# MiniCob.net
KiCad netlist of a schematic drawn in EAGLE
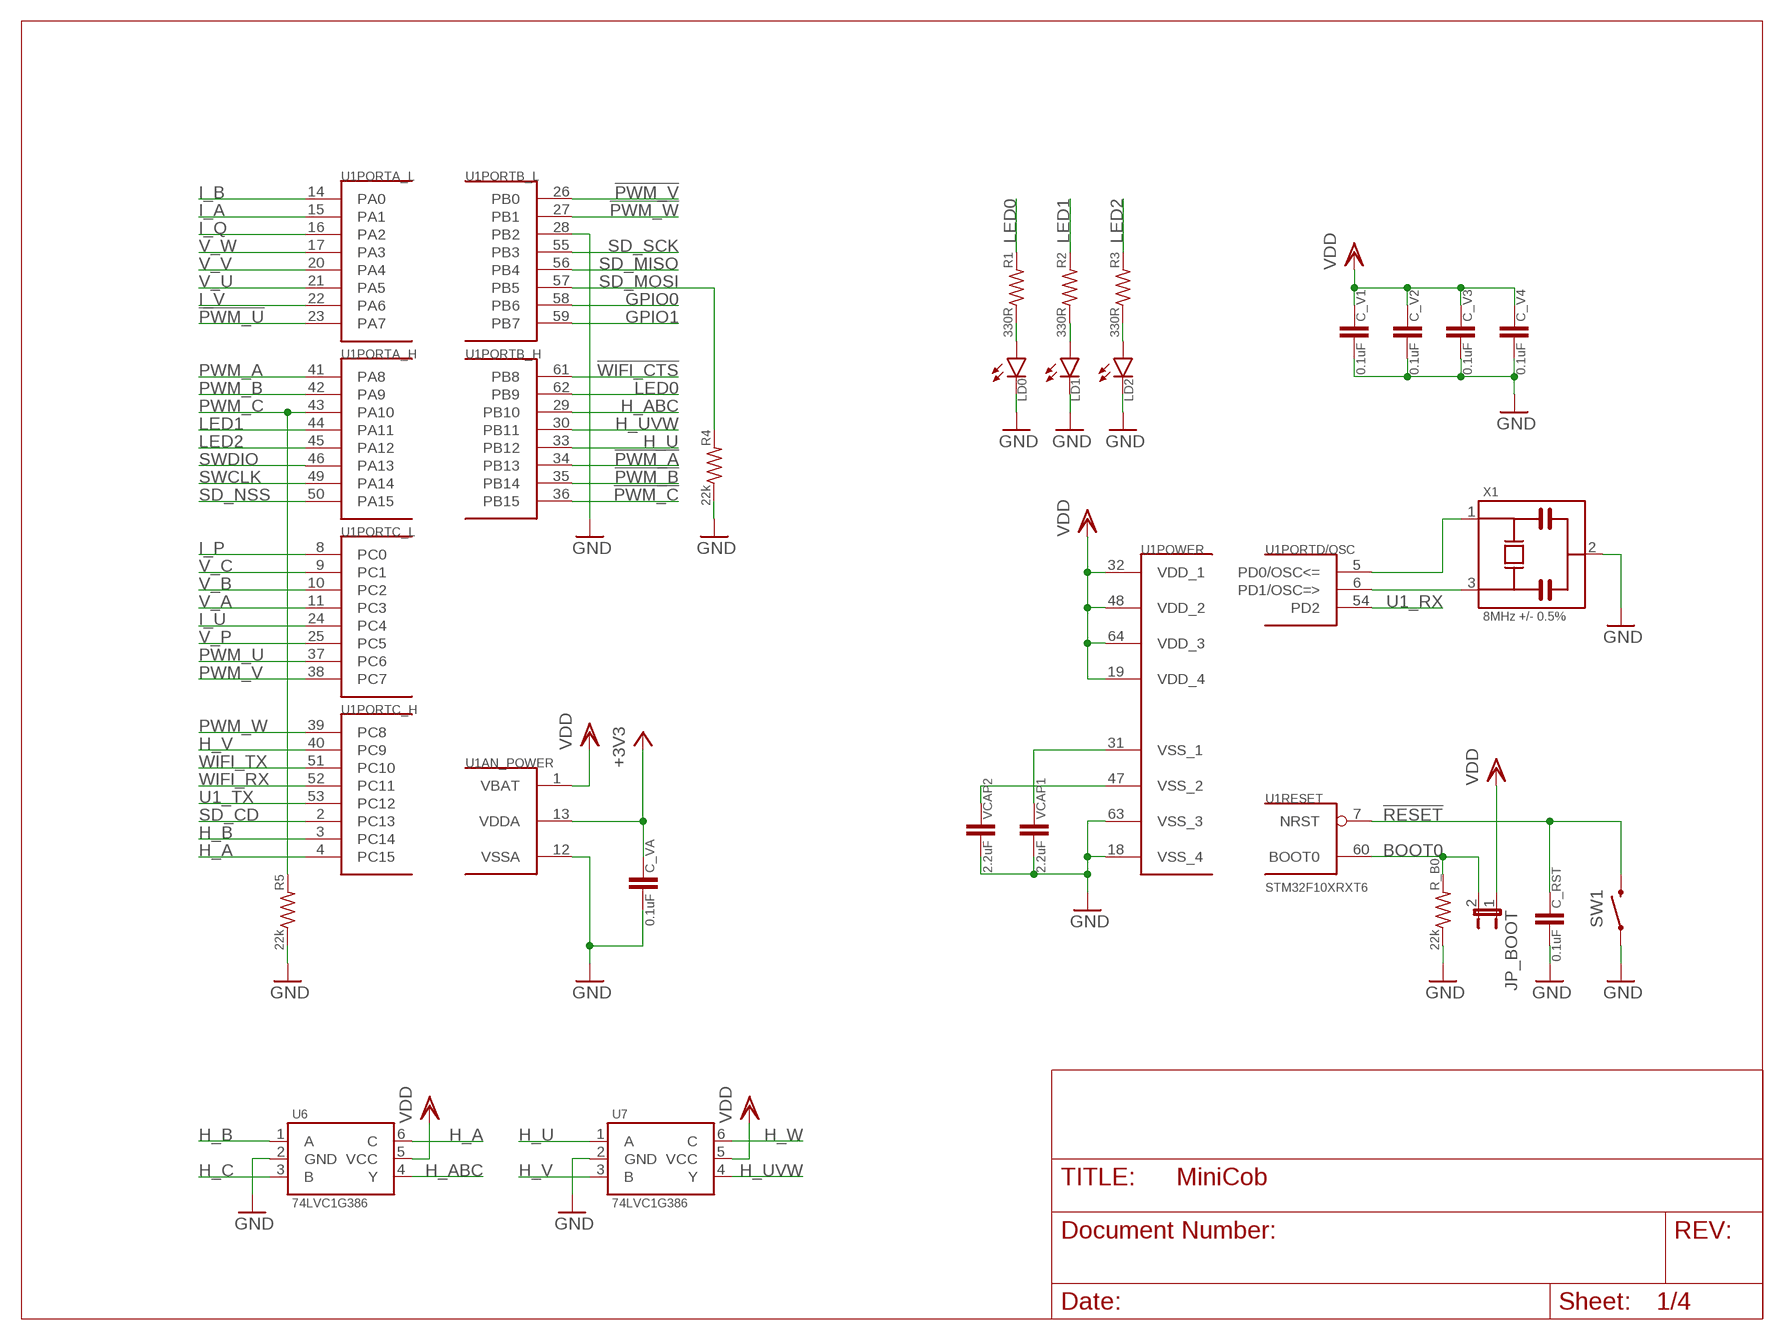
[diagram p0: schematic, sheet 1]
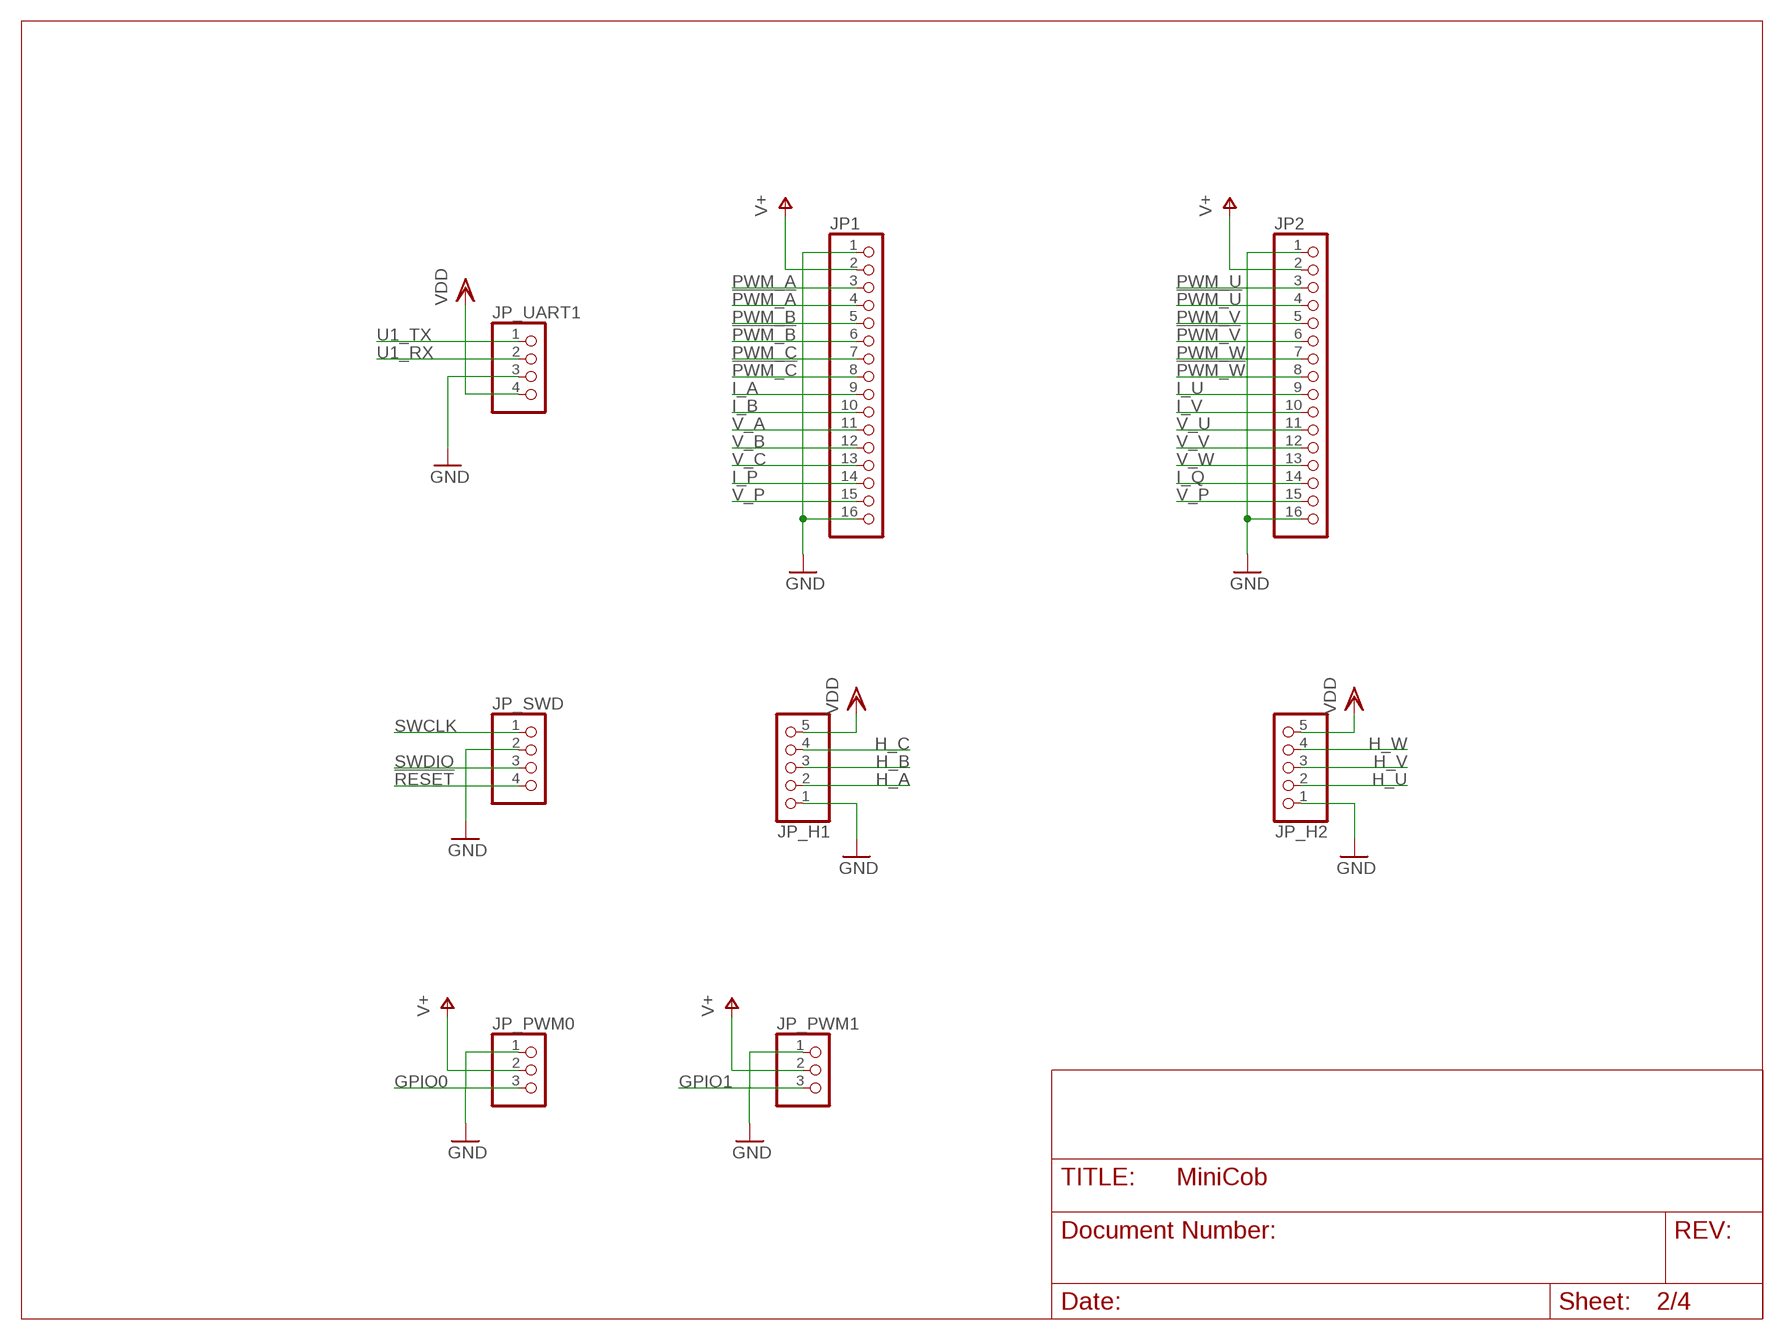
[diagram p1: schematic, sheet 2]
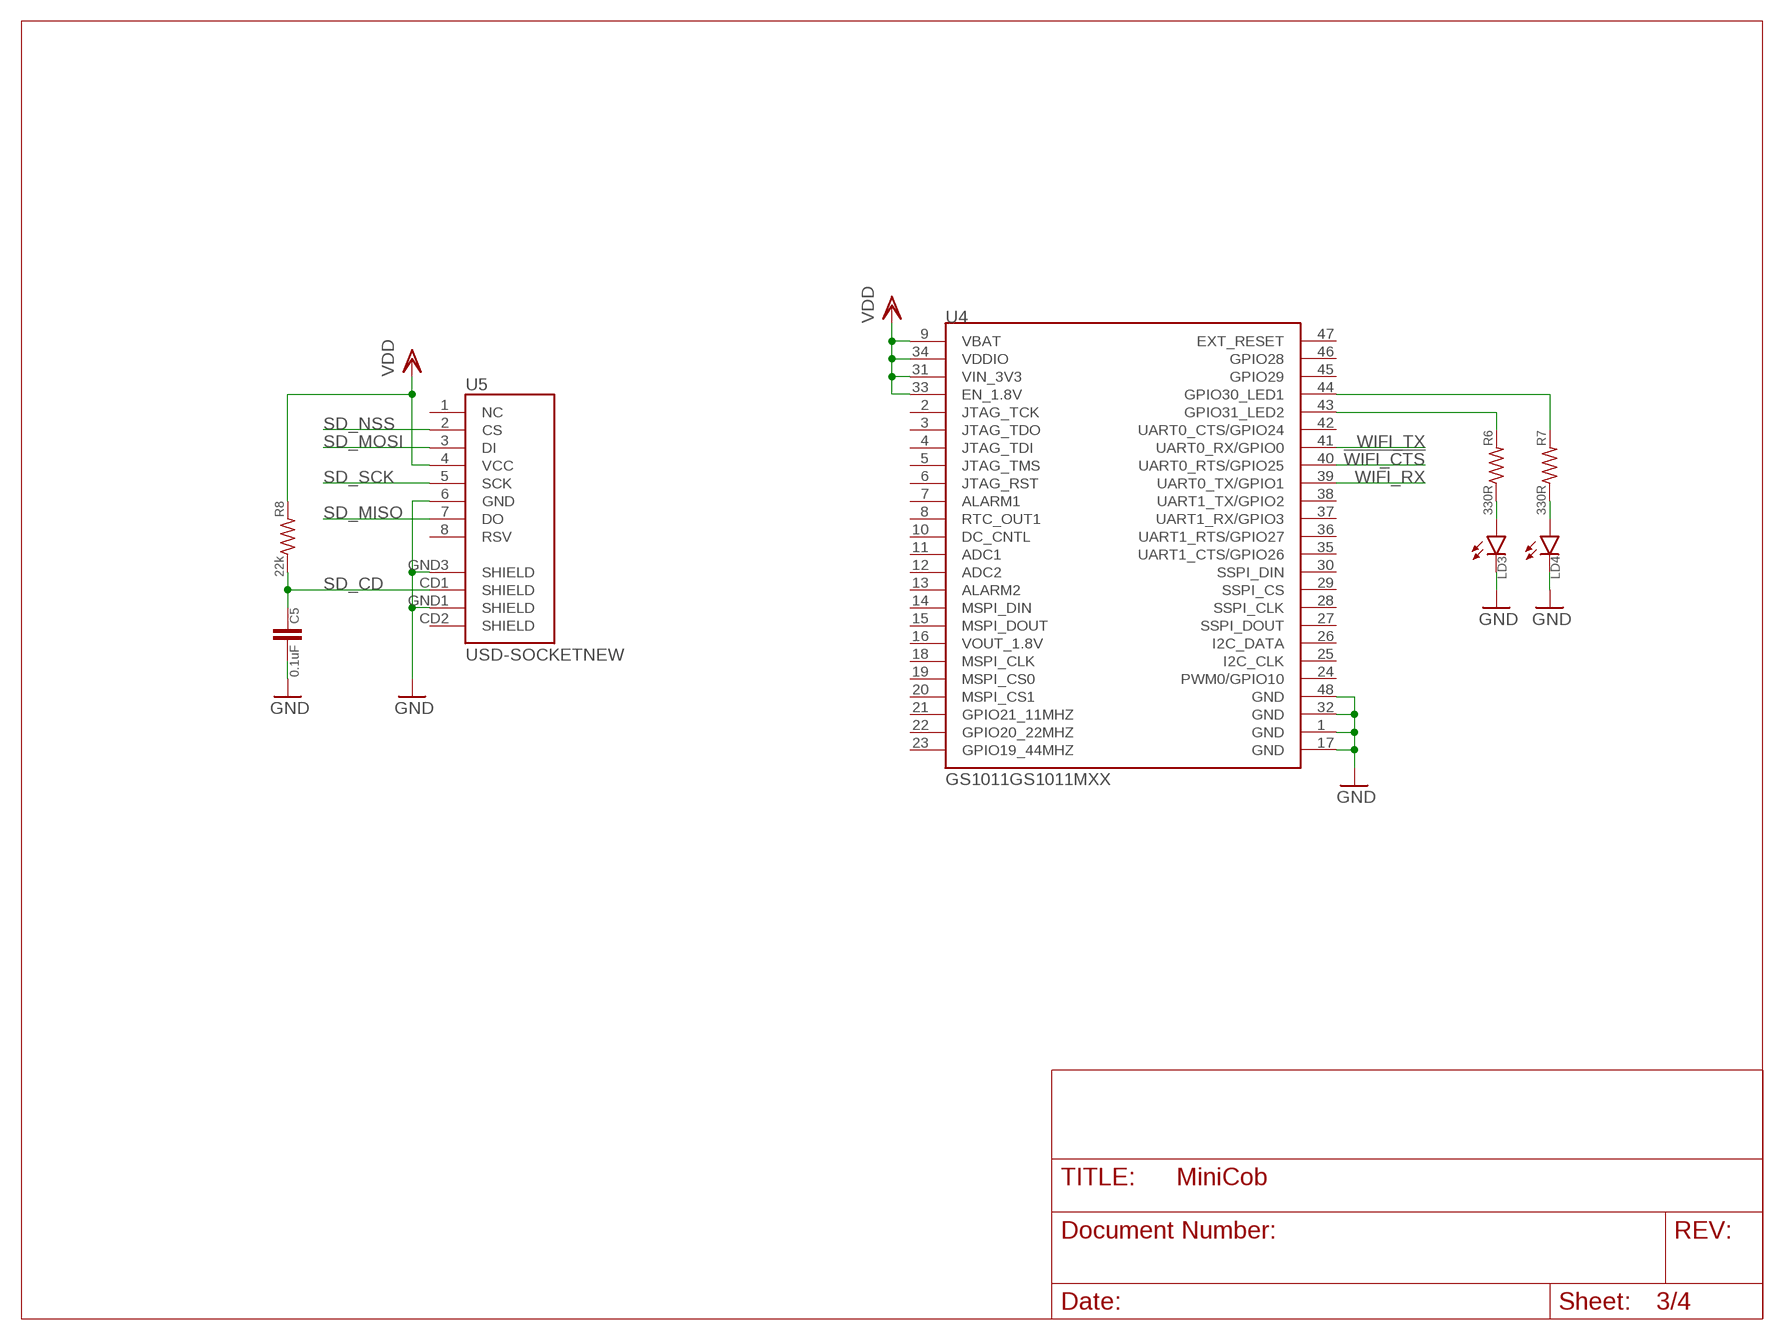
[diagram p2: schematic, sheet 3]
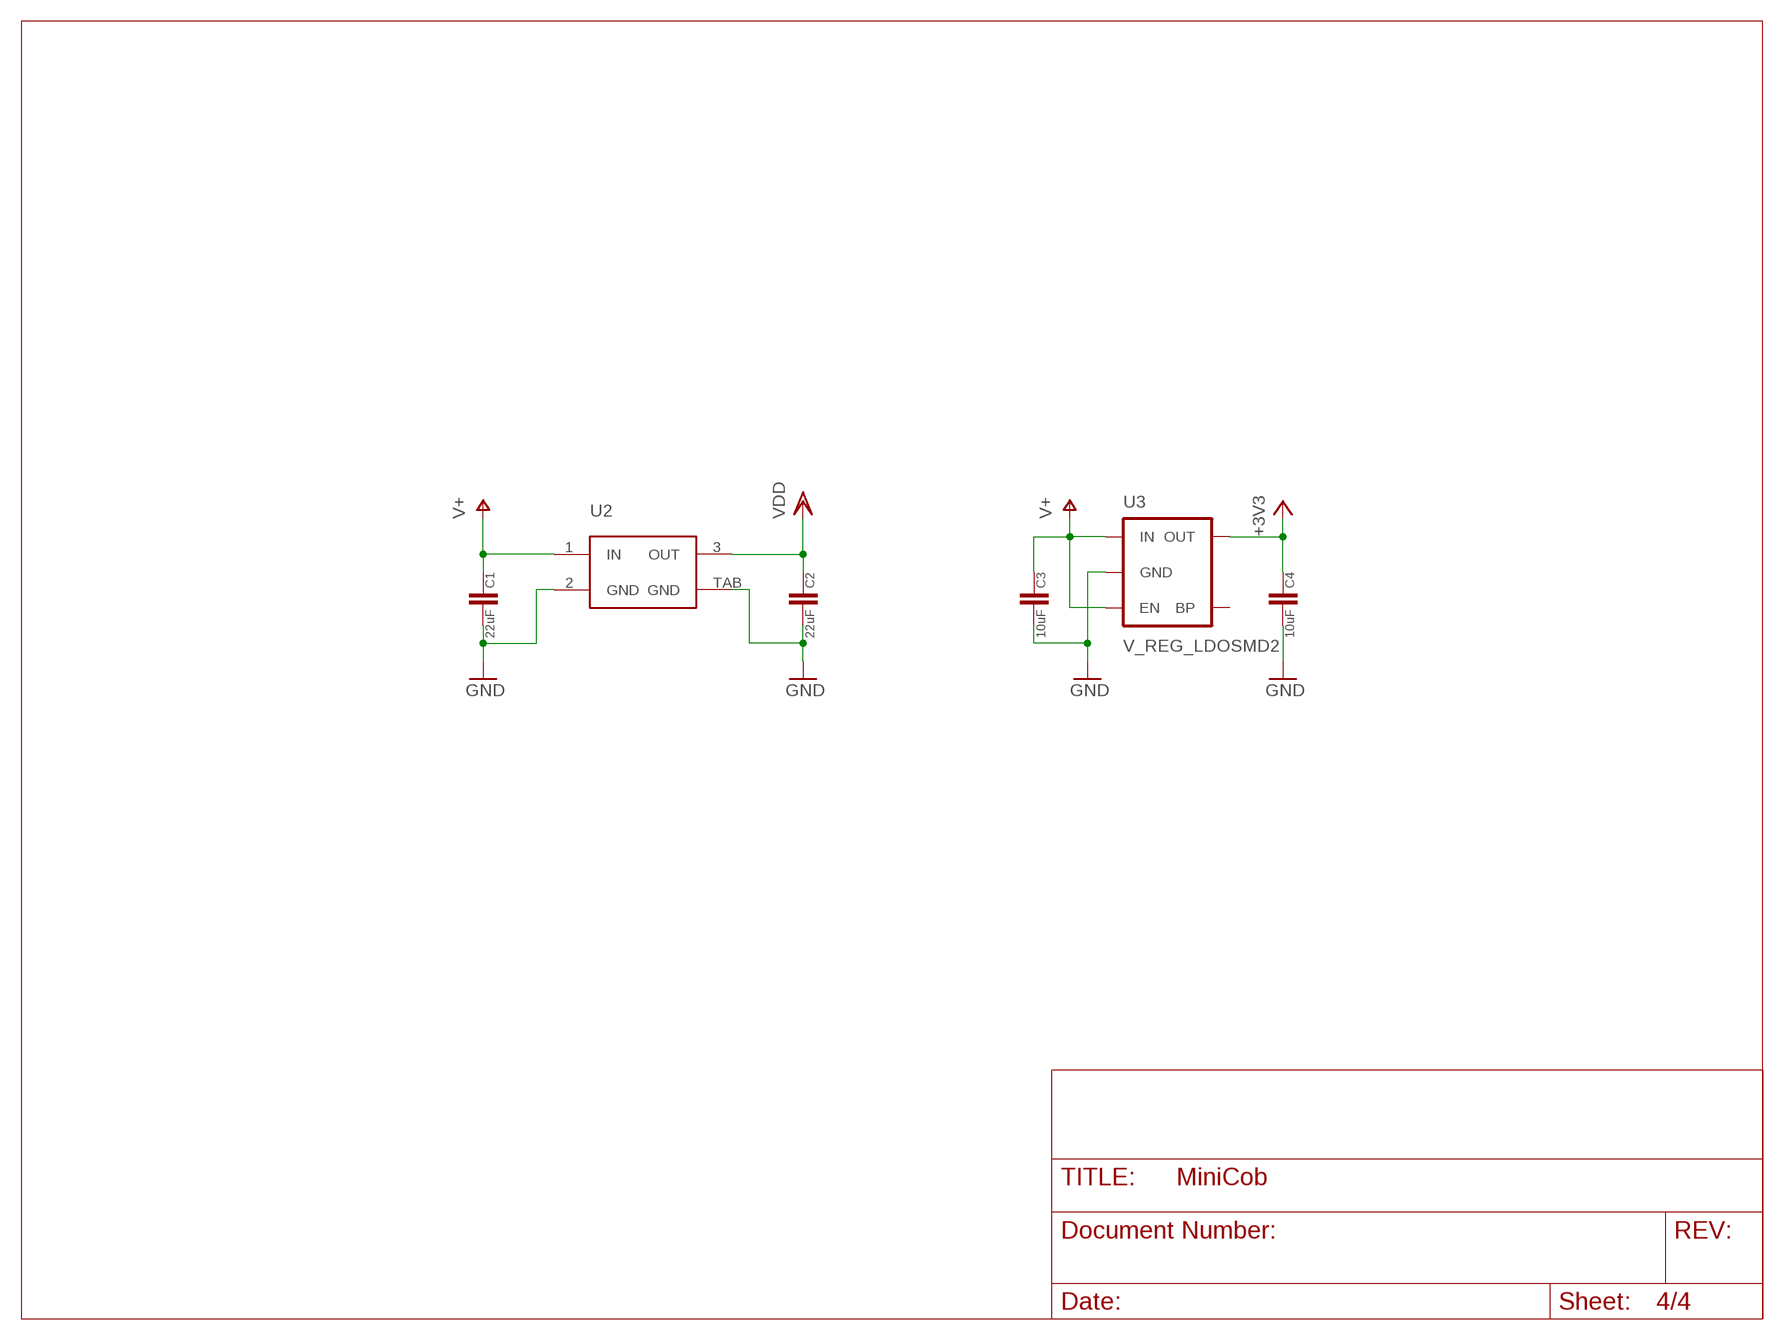
[diagram p3: schematic, sheet 4]

(export (version "E")
  (design (tool "Eeschema 10.0.6"))
  (components
    (comp (ref "JP1")
      (value "PINHD-1X16_2.54-S")
      (footprint "eagle-import:1X16-S")
      (libsource (lib "eagle-import") (part "PINHD-1X16_2.54-S"))
    )
    (comp (ref "JP2")
      (value "PINHD-1X16_2.54-S")
      (footprint "eagle-import:1X16-S")
      (libsource (lib "eagle-import") (part "PINHD-1X16_2.54-S"))
    )
    (comp (ref "JP_H1")
      (value "PINHD-1X05_2.54-S")
      (footprint "eagle-import:1X05-S")
      (libsource (lib "eagle-import") (part "PINHD-1X05_2.54-S"))
    )
    (comp (ref "JP_H2")
      (value "PINHD-1X05_2.54-S")
      (footprint "eagle-import:1X05-S")
      (libsource (lib "eagle-import") (part "PINHD-1X05_2.54-S"))
    )
    (comp (ref "JP_PWM0")
      (value "PINHD-1X03_2.54-S")
      (footprint "eagle-import:1X03-S")
      (libsource (lib "eagle-import") (part "PINHD-1X03_2.54-S"))
    )
    (comp (ref "JP_PWM1")
      (value "PINHD-1X03_2.54-S")
      (footprint "eagle-import:1X03-S")
      (libsource (lib "eagle-import") (part "PINHD-1X03_2.54-S"))
    )
    (comp (ref "JP_SWD")
      (value "PINHD-1X04_2.54-S")
      (footprint "eagle-import:1X04-S")
      (libsource (lib "eagle-import") (part "PINHD-1X04_2.54-S"))
    )
    (comp (ref "JP_UART1")
      (value "PINHD-1X04_2.54-S")
      (footprint "eagle-import:1X04-S")
      (libsource (lib "eagle-import") (part "PINHD-1X04_2.54-S"))
    )
    (comp (ref "C1")
      (value "22uF")
      (footprint "eagle-import:0805")
      (libsource (lib "eagle-import") (part "C0805"))
    )
    (comp (ref "C2")
      (value "22uF")
      (footprint "eagle-import:0805")
      (libsource (lib "eagle-import") (part "C0805"))
    )
    (comp (ref "C3")
      (value "10uF")
      (footprint "eagle-import:0805")
      (libsource (lib "eagle-import") (part "C0805"))
    )
    (comp (ref "C4")
      (value "10uF")
      (footprint "eagle-import:0805")
      (libsource (lib "eagle-import") (part "C0805"))
    )
    (comp (ref "U2")
      (value "MCP1826S")
      (footprint "eagle-import:SOT223-3L")
      (libsource (lib "eagle-import") (part "MCP1826S"))
    )
    (comp (ref "U3")
      (value "V_REG_LDOSMD2")
      (footprint "eagle-import:SC70")
      (libsource (lib "eagle-import") (part "V_REG_LDOSMD2"))
    )
    (comp (ref "C5")
      (value "0.1uF")
      (footprint "eagle-import:0603")
      (libsource (lib "eagle-import") (part "C0603"))
    )
    (comp (ref "LD3")
      (value "LED0805")
      (footprint "eagle-import:0805_POL")
      (libsource (lib "eagle-import") (part "LED0805"))
    )
    (comp (ref "LD4")
      (value "LED0805")
      (footprint "eagle-import:0805_POL")
      (libsource (lib "eagle-import") (part "LED0805"))
    )
    (comp (ref "R6")
      (value "330R")
      (footprint "eagle-import:0603")
      (libsource (lib "eagle-import") (part "R0603"))
    )
    (comp (ref "R7")
      (value "330R")
      (footprint "eagle-import:0603")
      (libsource (lib "eagle-import") (part "R0603"))
    )
    (comp (ref "R8")
      (value "22k")
      (footprint "eagle-import:0603")
      (libsource (lib "eagle-import") (part "R0603"))
    )
    (comp (ref "U4")
      (value "GS1011GS1011MXX")
      (footprint "eagle-import:GS1011MXX")
      (libsource (lib "eagle-import") (part "GS1011GS1011MXX"))
    )
    (comp (ref "U5")
      (value "USD-SOCKETNEW")
      (footprint "eagle-import:MICRO-SD-SOCKET-PP")
      (libsource (lib "eagle-import") (part "USD-SOCKETNEW"))
    )
    (comp (ref "C_RST")
      (value "0.1uF")
      (footprint "eagle-import:0603")
      (libsource (lib "eagle-import") (part "C0603"))
    )
    (comp (ref "C_V1")
      (value "0.1uF")
      (footprint "eagle-import:0603")
      (libsource (lib "eagle-import") (part "C0603"))
    )
    (comp (ref "C_V2")
      (value "0.1uF")
      (footprint "eagle-import:0603")
      (libsource (lib "eagle-import") (part "C0603"))
    )
    (comp (ref "C_V3")
      (value "0.1uF")
      (footprint "eagle-import:0603")
      (libsource (lib "eagle-import") (part "C0603"))
    )
    (comp (ref "C_V4")
      (value "0.1uF")
      (footprint "eagle-import:0603")
      (libsource (lib "eagle-import") (part "C0603"))
    )
    (comp (ref "C_VA")
      (value "0.1uF")
      (footprint "eagle-import:0603")
      (libsource (lib "eagle-import") (part "C0603"))
    )
    (comp (ref "JP_BOOT")
      (value "JUMPER-2PTH")
      (footprint "eagle-import:1X02")
      (libsource (lib "eagle-import") (part "JUMPER-2PTH"))
    )
    (comp (ref "LD0")
      (value "LED0805")
      (footprint "eagle-import:0805_POL")
      (libsource (lib "eagle-import") (part "LED0805"))
    )
    (comp (ref "LD1")
      (value "LED0805")
      (footprint "eagle-import:0805_POL")
      (libsource (lib "eagle-import") (part "LED0805"))
    )
    (comp (ref "LD2")
      (value "LED0805")
      (footprint "eagle-import:0805_POL")
      (libsource (lib "eagle-import") (part "LED0805"))
    )
    (comp (ref "R1")
      (value "330R")
      (footprint "eagle-import:0603")
      (libsource (lib "eagle-import") (part "R0603"))
    )
    (comp (ref "R2")
      (value "330R")
      (footprint "eagle-import:0603")
      (libsource (lib "eagle-import") (part "R0603"))
    )
    (comp (ref "R3")
      (value "330R")
      (footprint "eagle-import:0603")
      (libsource (lib "eagle-import") (part "R0603"))
    )
    (comp (ref "R4")
      (value "22k")
      (footprint "eagle-import:0603")
      (libsource (lib "eagle-import") (part "R0603"))
    )
    (comp (ref "R5")
      (value "22k")
      (footprint "eagle-import:0603")
      (libsource (lib "eagle-import") (part "R0603"))
    )
    (comp (ref "R_B0")
      (value "22k")
      (footprint "eagle-import:0603")
      (libsource (lib "eagle-import") (part "R0603"))
    )
    (comp (ref "SW1")
      (value "SWITCH_SPST-NO")
      (footprint "eagle-import:B3U-1000P")
      (libsource (lib "eagle-import") (part "SWITCH_SPST-NO"))
    )
    (comp (ref "U1")
      (value "STM32F10XRXT6")
      (footprint "eagle-import:TQFP64")
      (libsource (lib "eagle-import") (part "STM32F10XRXT6"))
    )
    (comp (ref "U6")
      (value "74LVC1G386")
      (footprint "eagle-import:SC-70")
      (libsource (lib "eagle-import") (part "74LVC1G386"))
    )
    (comp (ref "U7")
      (value "74LVC1G386")
      (footprint "eagle-import:SC-70")
      (libsource (lib "eagle-import") (part "74LVC1G386"))
    )
    (comp (ref "VCAP1")
      (value "2.2uF")
      (footprint "eagle-import:0603")
      (libsource (lib "eagle-import") (part "C0603"))
    )
    (comp (ref "VCAP2")
      (value "2.2uF")
      (footprint "eagle-import:0603")
      (libsource (lib "eagle-import") (part "C0603"))
    )
    (comp (ref "X1")
      (value "8MHz +/- 0.5%")
      (footprint "eagle-import:MURATA_CSTCE")
      (libsource (lib "eagle-import") (part "MURATA_CSTCE"))
    )
  )
  (nets
    (net (code "1") (name "+3V3") (class "Default")
      (node (ref "C4") (pin "1") (pinfunction "1_1") (pintype "passive"))
      (node (ref "C_VA") (pin "1") (pinfunction "1_1") (pintype "passive"))
      (node (ref "U1") (pin "13") (pinfunction "VDDA_13") (pintype "power_in"))
      (node (ref "U3") (pin "5") (pinfunction "OUT_5") (pintype "passive"))
    )
    (net (code "2") (name "BOOT0") (class "Default")
      (node (ref "JP_BOOT") (pin "2") (pinfunction "2_2") (pintype "passive"))
      (node (ref "R_B0") (pin "2") (pinfunction "2_2") (pintype "passive"))
      (node (ref "U1") (pin "60") (pinfunction "BOOT0_60") (pintype "input"))
    )
    (net (code "3") (name "GND") (class "Default")
      (node (ref "C1") (pin "2") (pinfunction "2_2") (pintype "passive"))
      (node (ref "C2") (pin "2") (pinfunction "2_2") (pintype "passive"))
      (node (ref "C3") (pin "2") (pinfunction "2_2") (pintype "passive"))
      (node (ref "C4") (pin "2") (pinfunction "2_2") (pintype "passive"))
      (node (ref "C5") (pin "2") (pinfunction "2_2") (pintype "passive"))
      (node (ref "C_RST") (pin "2") (pinfunction "2_2") (pintype "passive"))
      (node (ref "C_V1") (pin "2") (pinfunction "2_2") (pintype "passive"))
      (node (ref "C_V2") (pin "2") (pinfunction "2_2") (pintype "passive"))
      (node (ref "C_V3") (pin "2") (pinfunction "2_2") (pintype "passive"))
      (node (ref "C_V4") (pin "2") (pinfunction "2_2") (pintype "passive"))
      (node (ref "C_VA") (pin "2") (pinfunction "2_2") (pintype "passive"))
      (node (ref "JP1") (pin "1") (pinfunction "1_1") (pintype "passive"))
      (node (ref "JP1") (pin "16") (pinfunction "16_16") (pintype "passive"))
      (node (ref "JP2") (pin "1") (pinfunction "1_1") (pintype "passive"))
      (node (ref "JP2") (pin "16") (pinfunction "16_16") (pintype "passive"))
      (node (ref "JP_H1") (pin "1") (pinfunction "1_1") (pintype "passive"))
      (node (ref "JP_H2") (pin "1") (pinfunction "1_1") (pintype "passive"))
      (node (ref "JP_PWM0") (pin "1") (pinfunction "1_1") (pintype "passive"))
      (node (ref "JP_PWM1") (pin "1") (pinfunction "1_1") (pintype "passive"))
      (node (ref "JP_SWD") (pin "2") (pinfunction "2_2") (pintype "passive"))
      (node (ref "JP_UART1") (pin "3") (pinfunction "3_3") (pintype "passive"))
      (node (ref "LD0") (pin "-") (pinfunction "C_-") (pintype "passive"))
      (node (ref "LD1") (pin "-") (pinfunction "C_-") (pintype "passive"))
      (node (ref "LD2") (pin "-") (pinfunction "C_-") (pintype "passive"))
      (node (ref "LD3") (pin "-") (pinfunction "C_-") (pintype "passive"))
      (node (ref "LD4") (pin "-") (pinfunction "C_-") (pintype "passive"))
      (node (ref "R4") (pin "1") (pinfunction "1_1") (pintype "passive"))
      (node (ref "R5") (pin "1") (pinfunction "1_1") (pintype "passive"))
      (node (ref "R_B0") (pin "1") (pinfunction "1_1") (pintype "passive"))
      (node (ref "SW1") (pin "1") (pinfunction "1_1") (pintype "passive"))
      (node (ref "U1") (pin "12") (pinfunction "VSSA_12") (pintype "power_in"))
      (node (ref "U1") (pin "18") (pinfunction "VSS_4_18") (pintype "power_in"))
      (node (ref "U1") (pin "28") (pinfunction "PB2_28") (pintype "bidirectional"))
      (node (ref "U1") (pin "63") (pinfunction "VSS_3_63") (pintype "power_in"))
      (node (ref "U2") (pin "2") (pinfunction "GND_2") (pintype "passive"))
      (node (ref "U2") (pin "TAB") (pinfunction "GND_TAB") (pintype "passive"))
      (node (ref "U3") (pin "2") (pinfunction "GND_2") (pintype "input"))
      (node (ref "U4") (pin "1") (pinfunction "GND_1") (pintype "bidirectional"))
      (node (ref "U4") (pin "17") (pinfunction "GND_17") (pintype "bidirectional"))
      (node (ref "U4") (pin "32") (pinfunction "GND_32") (pintype "bidirectional"))
      (node (ref "U4") (pin "48") (pinfunction "GND_48") (pintype "bidirectional"))
      (node (ref "U5") (pin "6") (pinfunction "GND_6") (pintype "bidirectional"))
      (node (ref "U5") (pin "GND1") (pinfunction "SHIELD_GND1") (pintype "bidirectional"))
      (node (ref "U5") (pin "GND3") (pinfunction "SHIELD_GND3") (pintype "bidirectional"))
      (node (ref "U6") (pin "2") (pinfunction "GND_2") (pintype "power_in"))
      (node (ref "U7") (pin "2") (pinfunction "GND_2") (pintype "power_in"))
      (node (ref "VCAP1") (pin "2") (pinfunction "2_2") (pintype "passive"))
      (node (ref "VCAP2") (pin "2") (pinfunction "2_2") (pintype "passive"))
      (node (ref "X1") (pin "2") (pinfunction "P$2_2") (pintype "bidirectional"))
    )
    (net (code "4") (name "GPIO0") (class "Default")
      (node (ref "JP_PWM0") (pin "3") (pinfunction "3_3") (pintype "passive"))
      (node (ref "U1") (pin "58") (pinfunction "PB6_58") (pintype "bidirectional"))
    )
    (net (code "5") (name "GPIO1") (class "Default")
      (node (ref "JP_PWM1") (pin "3") (pinfunction "3_3") (pintype "passive"))
      (node (ref "U1") (pin "59") (pinfunction "PB7_59") (pintype "bidirectional"))
    )
    (net (code "6") (name "H_A") (class "Default")
      (node (ref "JP_H1") (pin "2") (pinfunction "2_2") (pintype "passive"))
      (node (ref "U1") (pin "4") (pinfunction "PC15_4") (pintype "bidirectional"))
      (node (ref "U6") (pin "6") (pinfunction "C_6") (pintype "input"))
    )
    (net (code "7") (name "H_ABC") (class "Default")
      (node (ref "U1") (pin "29") (pinfunction "PB10_29") (pintype "bidirectional"))
      (node (ref "U6") (pin "4") (pinfunction "Y_4") (pintype "output"))
    )
    (net (code "8") (name "H_B") (class "Default")
      (node (ref "JP_H1") (pin "3") (pinfunction "3_3") (pintype "passive"))
      (node (ref "U1") (pin "3") (pinfunction "PC14_3") (pintype "bidirectional"))
      (node (ref "U6") (pin "1") (pinfunction "A_1") (pintype "input"))
    )
    (net (code "9") (name "H_C") (class "Default")
      (node (ref "JP_H1") (pin "4") (pinfunction "4_4") (pintype "passive"))
      (node (ref "U6") (pin "3") (pinfunction "B_3") (pintype "input"))
    )
    (net (code "10") (name "H_U") (class "Default")
      (node (ref "JP_H2") (pin "2") (pinfunction "2_2") (pintype "passive"))
      (node (ref "U1") (pin "33") (pinfunction "PB12_33") (pintype "bidirectional"))
      (node (ref "U7") (pin "1") (pinfunction "A_1") (pintype "input"))
    )
    (net (code "11") (name "H_UVW") (class "Default")
      (node (ref "U1") (pin "30") (pinfunction "PB11_30") (pintype "bidirectional"))
      (node (ref "U7") (pin "4") (pinfunction "Y_4") (pintype "output"))
    )
    (net (code "12") (name "H_V") (class "Default")
      (node (ref "JP_H2") (pin "3") (pinfunction "3_3") (pintype "passive"))
      (node (ref "U1") (pin "40") (pinfunction "PC9_40") (pintype "bidirectional"))
      (node (ref "U7") (pin "3") (pinfunction "B_3") (pintype "input"))
    )
    (net (code "13") (name "H_W") (class "Default")
      (node (ref "JP_H2") (pin "4") (pinfunction "4_4") (pintype "passive"))
      (node (ref "U7") (pin "6") (pinfunction "C_6") (pintype "input"))
    )
    (net (code "14") (name "I_A") (class "Default")
      (node (ref "JP1") (pin "9") (pinfunction "9_9") (pintype "passive"))
      (node (ref "U1") (pin "15") (pinfunction "PA1_15") (pintype "bidirectional"))
    )
    (net (code "15") (name "I_B") (class "Default")
      (node (ref "JP1") (pin "10") (pinfunction "10_10") (pintype "passive"))
      (node (ref "U1") (pin "14") (pinfunction "PA0_14") (pintype "bidirectional"))
    )
    (net (code "16") (name "I_P") (class "Default")
      (node (ref "JP1") (pin "14") (pinfunction "14_14") (pintype "passive"))
      (node (ref "U1") (pin "8") (pinfunction "PC0_8") (pintype "bidirectional"))
    )
    (net (code "17") (name "I_Q") (class "Default")
      (node (ref "JP2") (pin "14") (pinfunction "14_14") (pintype "passive"))
      (node (ref "U1") (pin "16") (pinfunction "PA2_16") (pintype "bidirectional"))
    )
    (net (code "18") (name "I_U") (class "Default")
      (node (ref "JP2") (pin "9") (pinfunction "9_9") (pintype "passive"))
      (node (ref "U1") (pin "24") (pinfunction "PC4_24") (pintype "bidirectional"))
    )
    (net (code "19") (name "I_V") (class "Default")
      (node (ref "JP2") (pin "10") (pinfunction "10_10") (pintype "passive"))
      (node (ref "U1") (pin "22") (pinfunction "PA6_22") (pintype "bidirectional"))
    )
    (net (code "20") (name "LED0") (class "Default")
      (node (ref "R1") (pin "2") (pinfunction "2_2") (pintype "passive"))
      (node (ref "U1") (pin "62") (pinfunction "PB9_62") (pintype "bidirectional"))
    )
    (net (code "21") (name "LED1") (class "Default")
      (node (ref "R2") (pin "2") (pinfunction "2_2") (pintype "passive"))
      (node (ref "U1") (pin "44") (pinfunction "PA11_44") (pintype "bidirectional"))
    )
    (net (code "22") (name "LED2") (class "Default")
      (node (ref "R3") (pin "2") (pinfunction "2_2") (pintype "passive"))
      (node (ref "U1") (pin "45") (pinfunction "PA12_45") (pintype "bidirectional"))
    )
    (net (code "23") (name "Net-(LD0-A)") (class "Default")
      (node (ref "LD0") (pin "+") (pinfunction "A_+") (pintype "passive"))
      (node (ref "R1") (pin "1") (pinfunction "1_1") (pintype "passive"))
    )
    (net (code "24") (name "Net-(LD1-A)") (class "Default")
      (node (ref "LD1") (pin "+") (pinfunction "A_+") (pintype "passive"))
      (node (ref "R2") (pin "1") (pinfunction "1_1") (pintype "passive"))
    )
    (net (code "25") (name "Net-(LD2-A)") (class "Default")
      (node (ref "LD2") (pin "+") (pinfunction "A_+") (pintype "passive"))
      (node (ref "R3") (pin "1") (pinfunction "1_1") (pintype "passive"))
    )
    (net (code "26") (name "Net-(LD3-A)") (class "Default")
      (node (ref "LD3") (pin "+") (pinfunction "A_+") (pintype "passive"))
      (node (ref "R6") (pin "1") (pinfunction "1_1") (pintype "passive"))
    )
    (net (code "27") (name "Net-(LD4-A)") (class "Default")
      (node (ref "LD4") (pin "+") (pinfunction "A_+") (pintype "passive"))
      (node (ref "R7") (pin "1") (pinfunction "1_1") (pintype "passive"))
    )
    (net (code "28") (name "Net-(U1H-PD0{slash}OSC<=)") (class "Default")
      (node (ref "U1") (pin "5") (pinfunction "PD0/OSC<=_5") (pintype "bidirectional"))
      (node (ref "X1") (pin "1") (pinfunction "P$1_1") (pintype "bidirectional"))
    )
    (net (code "29") (name "Net-(U1H-PD1{slash}OSC=>)") (class "Default")
      (node (ref "U1") (pin "6") (pinfunction "PD1/OSC=>_6") (pintype "bidirectional"))
      (node (ref "X1") (pin "3") (pinfunction "P$3_3") (pintype "bidirectional"))
    )
    (net (code "30") (name "Net-(U1I-VSS_1)") (class "Default")
      (node (ref "U1") (pin "31") (pinfunction "VSS_1_31") (pintype "power_in"))
      (node (ref "VCAP1") (pin "1") (pinfunction "1_1") (pintype "passive"))
    )
    (net (code "31") (name "Net-(U1I-VSS_2)") (class "Default")
      (node (ref "U1") (pin "47") (pinfunction "VSS_2_47") (pintype "power_in"))
      (node (ref "VCAP2") (pin "1") (pinfunction "1_1") (pintype "passive"))
    )
    (net (code "32") (name "Net-(U4-GPIO30_LED1)") (class "Default")
      (node (ref "R7") (pin "2") (pinfunction "2_2") (pintype "passive"))
      (node (ref "U4") (pin "44") (pinfunction "GPIO30_LED1_44") (pintype "bidirectional"))
    )
    (net (code "33") (name "Net-(U4-GPIO31_LED2)") (class "Default")
      (node (ref "R6") (pin "2") (pinfunction "2_2") (pintype "passive"))
      (node (ref "U4") (pin "43") (pinfunction "GPIO31_LED2_43") (pintype "bidirectional"))
    )
    (net (code "34") (name "PWM_A") (class "Default")
      (node (ref "JP1") (pin "3") (pinfunction "3_3") (pintype "passive"))
      (node (ref "U1") (pin "41") (pinfunction "PA8_41") (pintype "bidirectional"))
    )
    (net (code "35") (name "PWM_B") (class "Default")
      (node (ref "JP1") (pin "5") (pinfunction "5_5") (pintype "passive"))
      (node (ref "U1") (pin "42") (pinfunction "PA9_42") (pintype "bidirectional"))
    )
    (net (code "36") (name "PWM_C") (class "Default")
      (node (ref "JP1") (pin "7") (pinfunction "7_7") (pintype "passive"))
      (node (ref "R5") (pin "2") (pinfunction "2_2") (pintype "passive"))
      (node (ref "U1") (pin "43") (pinfunction "PA10_43") (pintype "bidirectional"))
    )
    (net (code "37") (name "PWM_U") (class "Default")
      (node (ref "JP2") (pin "3") (pinfunction "3_3") (pintype "passive"))
      (node (ref "U1") (pin "37") (pinfunction "PC6_37") (pintype "bidirectional"))
    )
    (net (code "38") (name "PWM_V") (class "Default")
      (node (ref "JP2") (pin "5") (pinfunction "5_5") (pintype "passive"))
      (node (ref "U1") (pin "38") (pinfunction "PC7_38") (pintype "bidirectional"))
    )
    (net (code "39") (name "PWM_W") (class "Default")
      (node (ref "JP2") (pin "7") (pinfunction "7_7") (pintype "passive"))
      (node (ref "U1") (pin "39") (pinfunction "PC8_39") (pintype "bidirectional"))
    )
    (net (code "40") (name "SD_CD") (class "Default")
      (node (ref "C5") (pin "1") (pinfunction "1_1") (pintype "passive"))
      (node (ref "R8") (pin "1") (pinfunction "1_1") (pintype "passive"))
      (node (ref "U1") (pin "2") (pinfunction "PC13_2") (pintype "bidirectional"))
      (node (ref "U5") (pin "CD1") (pinfunction "SHIELD_CD1") (pintype "bidirectional"))
    )
    (net (code "41") (name "SD_MISO") (class "Default")
      (node (ref "U1") (pin "56") (pinfunction "PB4_56") (pintype "bidirectional"))
      (node (ref "U5") (pin "7") (pinfunction "DO_7") (pintype "bidirectional"))
    )
    (net (code "42") (name "SD_MOSI") (class "Default")
      (node (ref "R4") (pin "2") (pinfunction "2_2") (pintype "passive"))
      (node (ref "U1") (pin "57") (pinfunction "PB5_57") (pintype "bidirectional"))
      (node (ref "U5") (pin "3") (pinfunction "DI_3") (pintype "bidirectional"))
    )
    (net (code "43") (name "SD_NSS") (class "Default")
      (node (ref "U1") (pin "50") (pinfunction "PA15_50") (pintype "bidirectional"))
      (node (ref "U5") (pin "2") (pinfunction "CS_2") (pintype "bidirectional"))
    )
    (net (code "44") (name "SD_SCK") (class "Default")
      (node (ref "U1") (pin "55") (pinfunction "PB3_55") (pintype "bidirectional"))
      (node (ref "U5") (pin "5") (pinfunction "SCK_5") (pintype "bidirectional"))
    )
    (net (code "45") (name "SWCLK") (class "Default")
      (node (ref "JP_SWD") (pin "1") (pinfunction "1_1") (pintype "passive"))
      (node (ref "U1") (pin "49") (pinfunction "PA14_49") (pintype "bidirectional"))
    )
    (net (code "46") (name "SWDIO") (class "Default")
      (node (ref "JP_SWD") (pin "3") (pinfunction "3_3") (pintype "passive"))
      (node (ref "U1") (pin "46") (pinfunction "PA13_46") (pintype "bidirectional"))
    )
    (net (code "47") (name "U1_RX") (class "Default")
      (node (ref "JP_UART1") (pin "2") (pinfunction "2_2") (pintype "passive"))
      (node (ref "U1") (pin "54") (pinfunction "PD2_54") (pintype "bidirectional"))
    )
    (net (code "48") (name "U1_TX") (class "Default")
      (node (ref "JP_UART1") (pin "1") (pinfunction "1_1") (pintype "passive"))
      (node (ref "U1") (pin "53") (pinfunction "PC12_53") (pintype "bidirectional"))
    )
    (net (code "49") (name "V+") (class "Default")
      (node (ref "C1") (pin "1") (pinfunction "1_1") (pintype "passive"))
      (node (ref "C3") (pin "1") (pinfunction "1_1") (pintype "passive"))
      (node (ref "JP1") (pin "2") (pinfunction "2_2") (pintype "passive"))
      (node (ref "JP2") (pin "2") (pinfunction "2_2") (pintype "passive"))
      (node (ref "JP_PWM0") (pin "2") (pinfunction "2_2") (pintype "passive"))
      (node (ref "JP_PWM1") (pin "2") (pinfunction "2_2") (pintype "passive"))
      (node (ref "U2") (pin "1") (pinfunction "IN_1") (pintype "passive"))
      (node (ref "U3") (pin "1") (pinfunction "IN_1") (pintype "input"))
      (node (ref "U3") (pin "3") (pinfunction "EN_3") (pintype "input"))
    )
    (net (code "50") (name "VDD") (class "Default")
      (node (ref "C2") (pin "1") (pinfunction "1_1") (pintype "passive"))
      (node (ref "C_V1") (pin "1") (pinfunction "1_1") (pintype "passive"))
      (node (ref "C_V2") (pin "1") (pinfunction "1_1") (pintype "passive"))
      (node (ref "C_V3") (pin "1") (pinfunction "1_1") (pintype "passive"))
      (node (ref "C_V4") (pin "1") (pinfunction "1_1") (pintype "passive"))
      (node (ref "JP_BOOT") (pin "1") (pinfunction "1_1") (pintype "passive"))
      (node (ref "JP_H1") (pin "5") (pinfunction "5_5") (pintype "passive"))
      (node (ref "JP_H2") (pin "5") (pinfunction "5_5") (pintype "passive"))
      (node (ref "JP_UART1") (pin "4") (pinfunction "4_4") (pintype "passive"))
      (node (ref "R8") (pin "2") (pinfunction "2_2") (pintype "passive"))
      (node (ref "U1") (pin "1") (pinfunction "VBAT_1") (pintype "power_in"))
      (node (ref "U1") (pin "19") (pinfunction "VDD_4_19") (pintype "power_in"))
      (node (ref "U1") (pin "32") (pinfunction "VDD_1_32") (pintype "power_in"))
      (node (ref "U1") (pin "48") (pinfunction "VDD_2_48") (pintype "power_in"))
      (node (ref "U1") (pin "64") (pinfunction "VDD_3_64") (pintype "power_in"))
      (node (ref "U2") (pin "3") (pinfunction "OUT_3") (pintype "passive"))
      (node (ref "U4") (pin "31") (pinfunction "VIN_3V3_31") (pintype "bidirectional"))
      (node (ref "U4") (pin "33") (pinfunction "EN_1.8V_33") (pintype "bidirectional"))
      (node (ref "U4") (pin "34") (pinfunction "VDDIO_34") (pintype "bidirectional"))
      (node (ref "U4") (pin "9") (pinfunction "VBAT_9") (pintype "bidirectional"))
      (node (ref "U5") (pin "4") (pinfunction "VCC_4") (pintype "bidirectional"))
      (node (ref "U6") (pin "5") (pinfunction "VCC_5") (pintype "power_in"))
      (node (ref "U7") (pin "5") (pinfunction "VCC_5") (pintype "power_in"))
    )
    (net (code "51") (name "V_A") (class "Default")
      (node (ref "JP1") (pin "11") (pinfunction "11_11") (pintype "passive"))
      (node (ref "U1") (pin "11") (pinfunction "PC3_11") (pintype "bidirectional"))
    )
    (net (code "52") (name "V_B") (class "Default")
      (node (ref "JP1") (pin "12") (pinfunction "12_12") (pintype "passive"))
      (node (ref "U1") (pin "10") (pinfunction "PC2_10") (pintype "bidirectional"))
    )
    (net (code "53") (name "V_C") (class "Default")
      (node (ref "JP1") (pin "13") (pinfunction "13_13") (pintype "passive"))
      (node (ref "U1") (pin "9") (pinfunction "PC1_9") (pintype "bidirectional"))
    )
    (net (code "54") (name "V_P") (class "Default")
      (node (ref "JP1") (pin "15") (pinfunction "15_15") (pintype "passive"))
      (node (ref "JP2") (pin "15") (pinfunction "15_15") (pintype "passive"))
      (node (ref "U1") (pin "25") (pinfunction "PC5_25") (pintype "bidirectional"))
    )
    (net (code "55") (name "V_U") (class "Default")
      (node (ref "JP2") (pin "11") (pinfunction "11_11") (pintype "passive"))
      (node (ref "U1") (pin "21") (pinfunction "PA5_21") (pintype "bidirectional"))
    )
    (net (code "56") (name "V_V") (class "Default")
      (node (ref "JP2") (pin "12") (pinfunction "12_12") (pintype "passive"))
      (node (ref "U1") (pin "20") (pinfunction "PA4_20") (pintype "bidirectional"))
    )
    (net (code "57") (name "V_W") (class "Default")
      (node (ref "JP2") (pin "13") (pinfunction "13_13") (pintype "passive"))
      (node (ref "U1") (pin "17") (pinfunction "PA3_17") (pintype "bidirectional"))
    )
    (net (code "58") (name "WIFI_RX") (class "Default")
      (node (ref "U1") (pin "52") (pinfunction "PC11_52") (pintype "bidirectional"))
      (node (ref "U4") (pin "39") (pinfunction "UART0_TX/GPIO1_39") (pintype "bidirectional"))
    )
    (net (code "59") (name "WIFI_TX") (class "Default")
      (node (ref "U1") (pin "51") (pinfunction "PC10_51") (pintype "bidirectional"))
      (node (ref "U4") (pin "41") (pinfunction "UART0_RX/GPIO0_41") (pintype "bidirectional"))
    )
    (net (code "60") (name "unconnected-(U3-BP-Pad4)") (class "Default")
      (node (ref "U3") (pin "4") (pinfunction "BP_4") (pintype "input"))
    )
    (net (code "61") (name "unconnected-(U4-ADC1-Pad11)") (class "Default")
      (node (ref "U4") (pin "11") (pinfunction "ADC1_11") (pintype "bidirectional"))
    )
    (net (code "62") (name "unconnected-(U4-ADC2-Pad12)") (class "Default")
      (node (ref "U4") (pin "12") (pinfunction "ADC2_12") (pintype "bidirectional"))
    )
    (net (code "63") (name "unconnected-(U4-ALARM1-Pad7)") (class "Default")
      (node (ref "U4") (pin "7") (pinfunction "ALARM1_7") (pintype "bidirectional"))
    )
    (net (code "64") (name "unconnected-(U4-ALARM2-Pad13)") (class "Default")
      (node (ref "U4") (pin "13") (pinfunction "ALARM2_13") (pintype "bidirectional"))
    )
    (net (code "65") (name "unconnected-(U4-DC_CNTL-Pad10)") (class "Default")
      (node (ref "U4") (pin "10") (pinfunction "DC_CNTL_10") (pintype "bidirectional"))
    )
    (net (code "66") (name "unconnected-(U4-EXT_RESET-Pad47)") (class "Default")
      (node (ref "U4") (pin "47") (pinfunction "EXT_RESET_47") (pintype "bidirectional"))
    )
    (net (code "67") (name "unconnected-(U4-GPIO19_44MHZ-Pad23)") (class "Default")
      (node (ref "U4") (pin "23") (pinfunction "GPIO19_44MHZ_23") (pintype "bidirectional"))
    )
    (net (code "68") (name "unconnected-(U4-GPIO20_22MHZ-Pad22)") (class "Default")
      (node (ref "U4") (pin "22") (pinfunction "GPIO20_22MHZ_22") (pintype "bidirectional"))
    )
    (net (code "69") (name "unconnected-(U4-GPIO21_11MHZ-Pad21)") (class "Default")
      (node (ref "U4") (pin "21") (pinfunction "GPIO21_11MHZ_21") (pintype "bidirectional"))
    )
    (net (code "70") (name "unconnected-(U4-GPIO28-Pad46)") (class "Default")
      (node (ref "U4") (pin "46") (pinfunction "GPIO28_46") (pintype "bidirectional"))
    )
    (net (code "71") (name "unconnected-(U4-GPIO29-Pad45)") (class "Default")
      (node (ref "U4") (pin "45") (pinfunction "GPIO29_45") (pintype "bidirectional"))
    )
    (net (code "72") (name "unconnected-(U4-I2C_CLK-Pad25)") (class "Default")
      (node (ref "U4") (pin "25") (pinfunction "I2C_CLK_25") (pintype "bidirectional"))
    )
    (net (code "73") (name "unconnected-(U4-I2C_DATA-Pad26)") (class "Default")
      (node (ref "U4") (pin "26") (pinfunction "I2C_DATA_26") (pintype "bidirectional"))
    )
    (net (code "74") (name "unconnected-(U4-JTAG_RST-Pad6)") (class "Default")
      (node (ref "U4") (pin "6") (pinfunction "JTAG_RST_6") (pintype "bidirectional"))
    )
    (net (code "75") (name "unconnected-(U4-JTAG_TCK-Pad2)") (class "Default")
      (node (ref "U4") (pin "2") (pinfunction "JTAG_TCK_2") (pintype "bidirectional"))
    )
    (net (code "76") (name "unconnected-(U4-JTAG_TDI-Pad4)") (class "Default")
      (node (ref "U4") (pin "4") (pinfunction "JTAG_TDI_4") (pintype "bidirectional"))
    )
    (net (code "77") (name "unconnected-(U4-JTAG_TDO-Pad3)") (class "Default")
      (node (ref "U4") (pin "3") (pinfunction "JTAG_TDO_3") (pintype "bidirectional"))
    )
    (net (code "78") (name "unconnected-(U4-JTAG_TMS-Pad5)") (class "Default")
      (node (ref "U4") (pin "5") (pinfunction "JTAG_TMS_5") (pintype "bidirectional"))
    )
    (net (code "79") (name "unconnected-(U4-MSPI_CLK-Pad18)") (class "Default")
      (node (ref "U4") (pin "18") (pinfunction "MSPI_CLK_18") (pintype "bidirectional"))
    )
    (net (code "80") (name "unconnected-(U4-MSPI_CS0-Pad19)") (class "Default")
      (node (ref "U4") (pin "19") (pinfunction "MSPI_CS0_19") (pintype "bidirectional"))
    )
    (net (code "81") (name "unconnected-(U4-MSPI_CS1-Pad20)") (class "Default")
      (node (ref "U4") (pin "20") (pinfunction "MSPI_CS1_20") (pintype "bidirectional"))
    )
    (net (code "82") (name "unconnected-(U4-MSPI_DIN-Pad14)") (class "Default")
      (node (ref "U4") (pin "14") (pinfunction "MSPI_DIN_14") (pintype "bidirectional"))
    )
    (net (code "83") (name "unconnected-(U4-MSPI_DOUT-Pad15)") (class "Default")
      (node (ref "U4") (pin "15") (pinfunction "MSPI_DOUT_15") (pintype "bidirectional"))
    )
    (net (code "84") (name "unconnected-(U4-PWM0{slash}GPIO10-Pad24)") (class "Default")
      (node (ref "U4") (pin "24") (pinfunction "PWM0/GPIO10_24") (pintype "bidirectional"))
    )
    (net (code "85") (name "unconnected-(U4-RTC_OUT1-Pad8)") (class "Default")
      (node (ref "U4") (pin "8") (pinfunction "RTC_OUT1_8") (pintype "bidirectional"))
    )
    (net (code "86") (name "unconnected-(U4-SSPI_CLK-Pad28)") (class "Default")
      (node (ref "U4") (pin "28") (pinfunction "SSPI_CLK_28") (pintype "bidirectional"))
    )
    (net (code "87") (name "unconnected-(U4-SSPI_CS-Pad29)") (class "Default")
      (node (ref "U4") (pin "29") (pinfunction "SSPI_CS_29") (pintype "bidirectional"))
    )
    (net (code "88") (name "unconnected-(U4-SSPI_DIN-Pad30)") (class "Default")
      (node (ref "U4") (pin "30") (pinfunction "SSPI_DIN_30") (pintype "bidirectional"))
    )
    (net (code "89") (name "unconnected-(U4-SSPI_DOUT-Pad27)") (class "Default")
      (node (ref "U4") (pin "27") (pinfunction "SSPI_DOUT_27") (pintype "bidirectional"))
    )
    (net (code "90") (name "unconnected-(U4-UART0_CTS{slash}GPIO24-Pad42)") (class "Default")
      (node (ref "U4") (pin "42") (pinfunction "UART0_CTS/GPIO24_42") (pintype "bidirectional"))
    )
    (net (code "91") (name "unconnected-(U4-UART1_CTS{slash}GPIO26-Pad35)") (class "Default")
      (node (ref "U4") (pin "35") (pinfunction "UART1_CTS/GPIO26_35") (pintype "bidirectional"))
    )
    (net (code "92") (name "unconnected-(U4-UART1_RTS{slash}GPIO27-Pad36)") (class "Default")
      (node (ref "U4") (pin "36") (pinfunction "UART1_RTS/GPIO27_36") (pintype "bidirectional"))
    )
    (net (code "93") (name "unconnected-(U4-UART1_RX{slash}GPIO3-Pad37)") (class "Default")
      (node (ref "U4") (pin "37") (pinfunction "UART1_RX/GPIO3_37") (pintype "bidirectional"))
    )
    (net (code "94") (name "unconnected-(U4-UART1_TX{slash}GPIO2-Pad38)") (class "Default")
      (node (ref "U4") (pin "38") (pinfunction "UART1_TX/GPIO2_38") (pintype "bidirectional"))
    )
    (net (code "95") (name "unconnected-(U4-VOUT_1.8V-Pad16)") (class "Default")
      (node (ref "U4") (pin "16") (pinfunction "VOUT_1.8V_16") (pintype "bidirectional"))
    )
    (net (code "96") (name "unconnected-(U5-NC-Pad1)") (class "Default")
      (node (ref "U5") (pin "1") (pinfunction "NC_1") (pintype "bidirectional"))
    )
    (net (code "97") (name "unconnected-(U5-RSV-Pad8)") (class "Default")
      (node (ref "U5") (pin "8") (pinfunction "RSV_8") (pintype "bidirectional"))
    )
    (net (code "98") (name "unconnected-(U5-SHIELD-PadCD2)") (class "Default")
      (node (ref "U5") (pin "CD2") (pinfunction "SHIELD_CD2") (pintype "bidirectional"))
    )
    (net (code "99") (name "~{PWM_A}") (class "Default")
      (node (ref "JP1") (pin "4") (pinfunction "4_4") (pintype "passive"))
      (node (ref "U1") (pin "34") (pinfunction "PB13_34") (pintype "bidirectional"))
    )
    (net (code "100") (name "~{PWM_B}") (class "Default")
      (node (ref "JP1") (pin "6") (pinfunction "6_6") (pintype "passive"))
      (node (ref "U1") (pin "35") (pinfunction "PB14_35") (pintype "bidirectional"))
    )
    (net (code "101") (name "~{PWM_C}") (class "Default")
      (node (ref "JP1") (pin "8") (pinfunction "8_8") (pintype "passive"))
      (node (ref "U1") (pin "36") (pinfunction "PB15_36") (pintype "bidirectional"))
    )
    (net (code "102") (name "~{PWM_U}") (class "Default")
      (node (ref "JP2") (pin "4") (pinfunction "4_4") (pintype "passive"))
      (node (ref "U1") (pin "23") (pinfunction "PA7_23") (pintype "bidirectional"))
    )
    (net (code "103") (name "~{PWM_V}") (class "Default")
      (node (ref "JP2") (pin "6") (pinfunction "6_6") (pintype "passive"))
      (node (ref "U1") (pin "26") (pinfunction "PB0_26") (pintype "bidirectional"))
    )
    (net (code "104") (name "~{PWM_W}") (class "Default")
      (node (ref "JP2") (pin "8") (pinfunction "8_8") (pintype "passive"))
      (node (ref "U1") (pin "27") (pinfunction "PB1_27") (pintype "bidirectional"))
    )
    (net (code "105") (name "~{RESET}") (class "Default")
      (node (ref "C_RST") (pin "1") (pinfunction "1_1") (pintype "passive"))
      (node (ref "JP_SWD") (pin "4") (pinfunction "4_4") (pintype "passive"))
      (node (ref "SW1") (pin "2") (pinfunction "2_2") (pintype "passive"))
      (node (ref "U1") (pin "7") (pinfunction "NRST_7") (pintype "input"))
    )
    (net (code "106") (name "~{WIFI_CTS}") (class "Default")
      (node (ref "U1") (pin "61") (pinfunction "PB8_61") (pintype "bidirectional"))
      (node (ref "U4") (pin "40") (pinfunction "UART0_RTS/GPIO25_40") (pintype "bidirectional"))
    )
  )
)
